# ANT_Miner_CtrlUnit_V1_2.net
KiCad netlist of a schematic drawn in Altium Designer
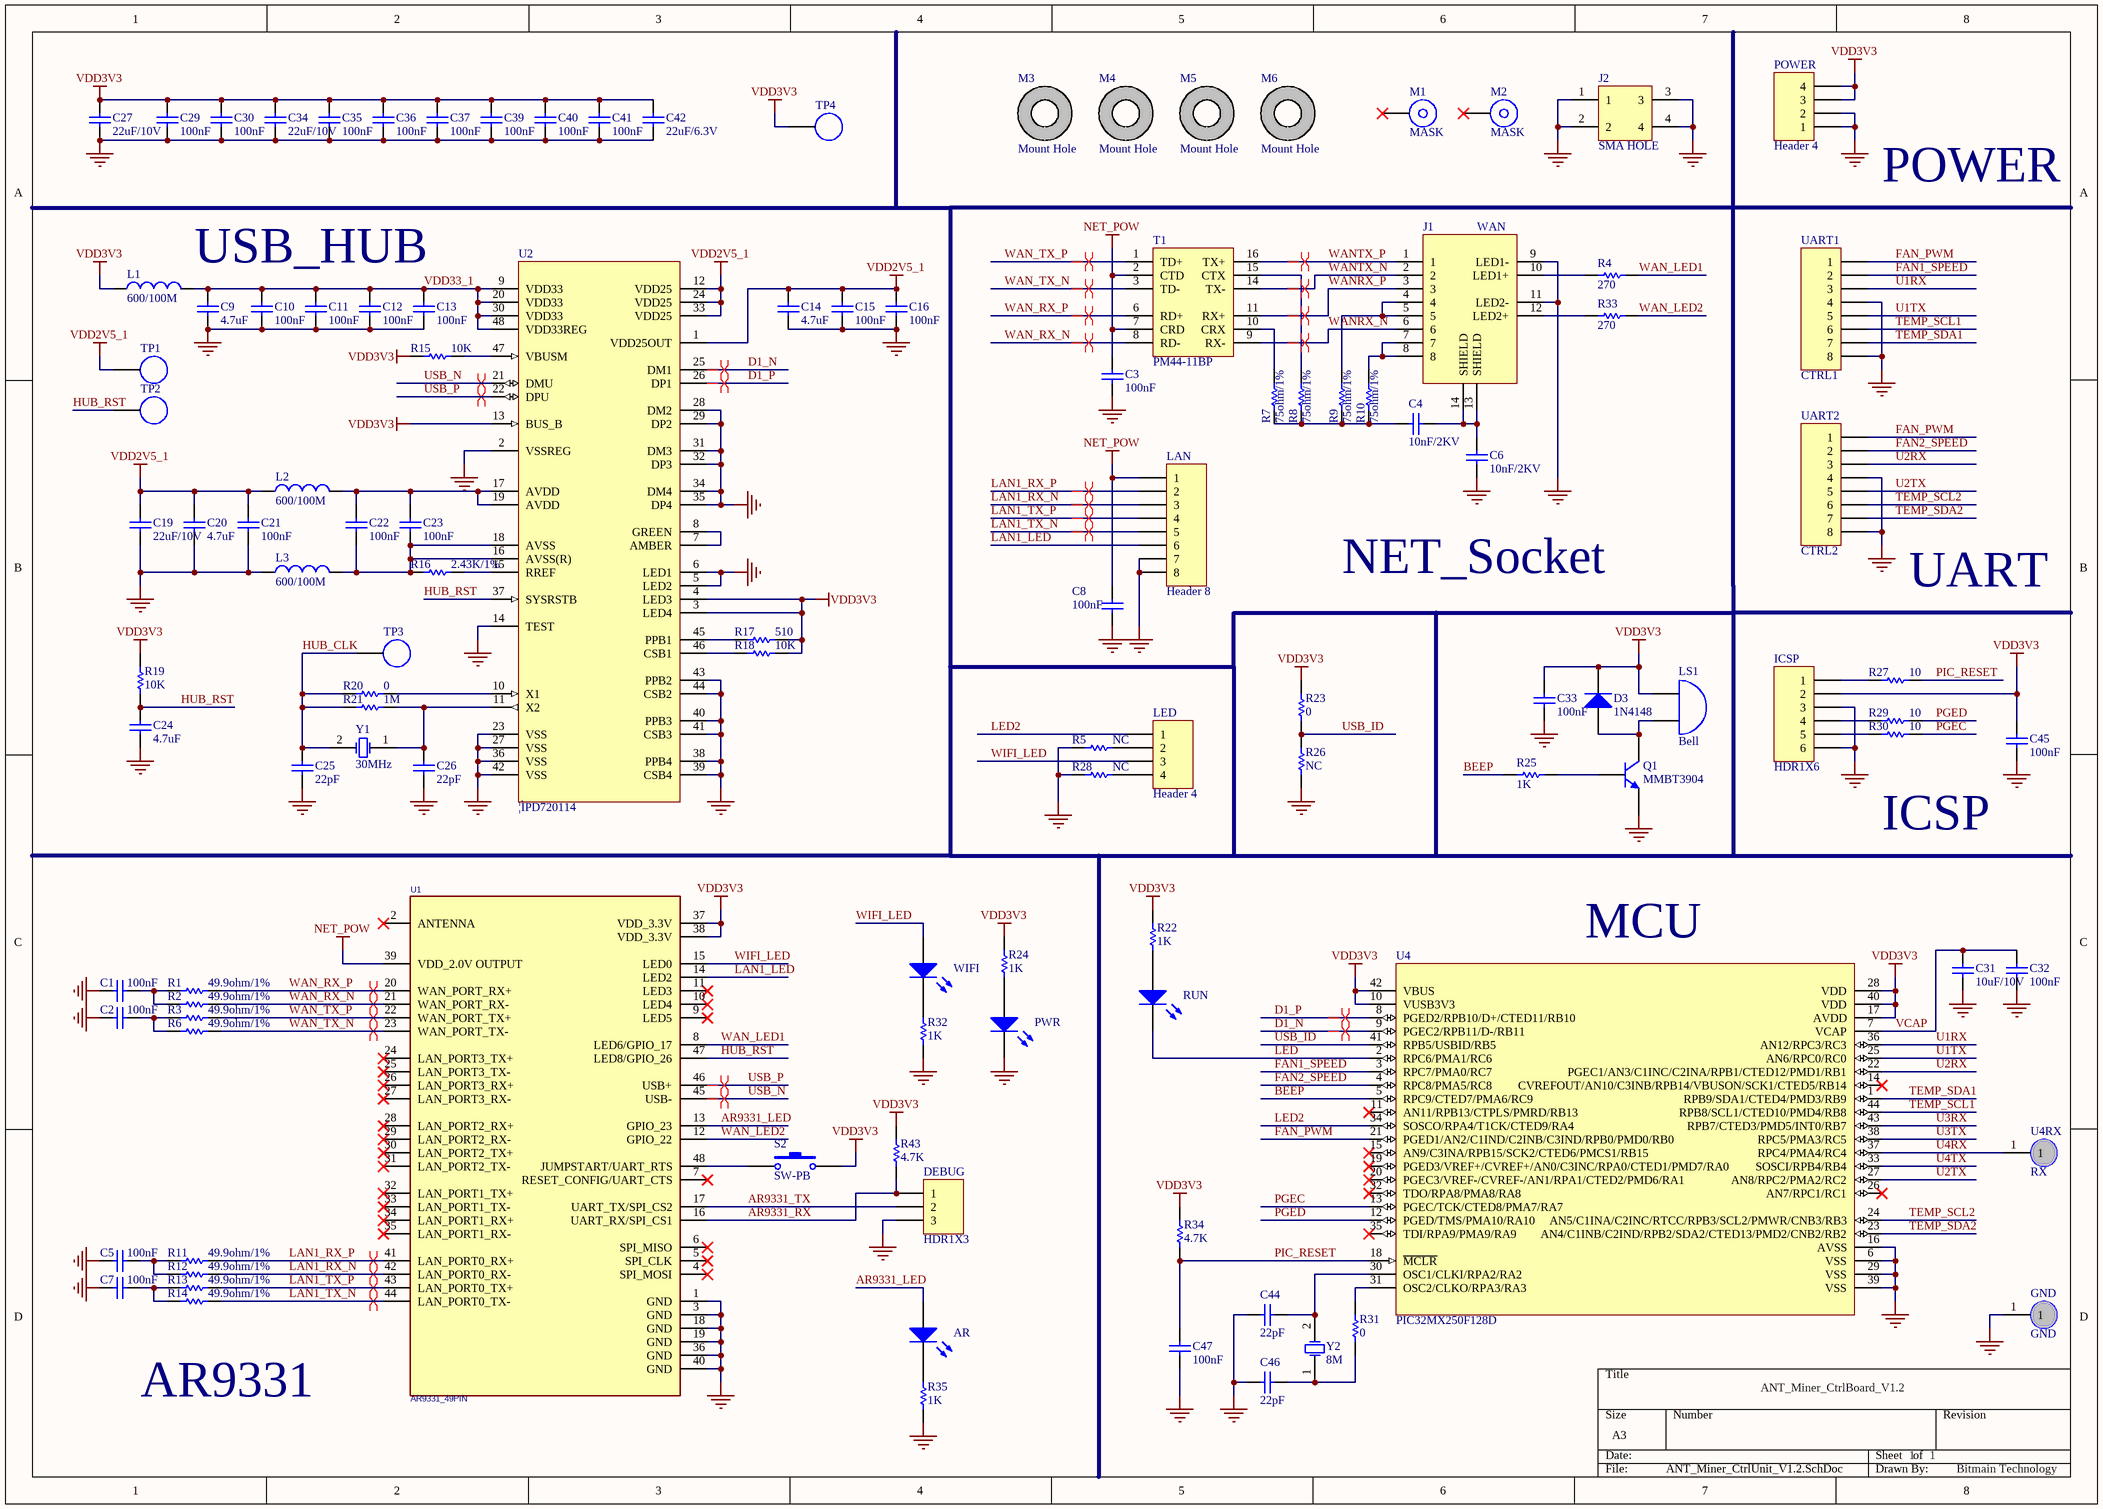
[diagram p0: ANT_Miner_CtrlUnit_V1.2.SchDoc]

(export (version "E")
  (design (tool "Eeschema 10.0.6"))
  (components
    (comp (ref "AR")
      (value "Green")
      (footprint "LED0603(1608)")
      (description "Typical INFRARED GaAs LED")
      (fields (field (name "PUBLISHER") "Altium Limited"))
      (libsource (lib "ANT_Miner_CtrlBoard_V1.1") (part "LED0"))
    )
    (comp (ref "C1")
      (value "100nF")
      (footprint "CC0603(1608)")
      (description "Capacitor (Semiconductor SIM Model)")
      (fields (field (name "PUBLISHER") "Altium Limited"))
      (libsource (lib "ANT_Miner_CtrlBoard_V1.1") (part "Cap Semi"))
    )
    (comp (ref "C2")
      (value "100nF")
      (footprint "CC0603(1608)")
      (description "Capacitor (Semiconductor SIM Model)")
      (fields (field (name "PUBLISHER") "Altium Limited"))
      (libsource (lib "ANT_Miner_CtrlBoard_V1.1") (part "Cap Semi"))
    )
    (comp (ref "C3")
      (value "100nF")
      (footprint "CC0603(1608)")
      (description "Capacitor (Semiconductor SIM Model)")
      (fields (field (name "PUBLISHER") "Altium Limited"))
      (libsource (lib "ANT_Miner_CtrlBoard_V1.1") (part "Cap Semi"))
    )
    (comp (ref "C4")
      (value "10nF/2KV")
      (footprint "1812")
      (description "Capacitor (Semiconductor SIM Model)")
      (fields (field (name "PUBLISHER") "Altium Limited"))
      (libsource (lib "ANT_Miner_CtrlBoard_V1.1") (part "Cap Semi"))
    )
    (comp (ref "C5")
      (value "100nF")
      (footprint "CC0603(1608)")
      (description "Capacitor (Semiconductor SIM Model)")
      (fields (field (name "PUBLISHER") "Altium Limited"))
      (libsource (lib "ANT_Miner_CtrlBoard_V1.1") (part "Cap Semi"))
    )
    (comp (ref "C6")
      (value "10nF/2KV")
      (footprint "1812")
      (description "Capacitor (Semiconductor SIM Model)")
      (fields (field (name "PUBLISHER") "Altium Limited"))
      (libsource (lib "ANT_Miner_CtrlBoard_V1.1") (part "Cap Semi"))
    )
    (comp (ref "C7")
      (value "100nF")
      (footprint "CC0603(1608)")
      (description "Capacitor (Semiconductor SIM Model)")
      (fields (field (name "PUBLISHER") "Altium Limited"))
      (libsource (lib "ANT_Miner_CtrlBoard_V1.1") (part "Cap Semi"))
    )
    (comp (ref "C8")
      (value "100nF")
      (footprint "CC0603(1608)")
      (description "Capacitor (Semiconductor SIM Model)")
      (fields (field (name "PUBLISHER") "Altium Limited"))
      (libsource (lib "ANT_Miner_CtrlBoard_V1.1") (part "Cap Semi"))
    )
    (comp (ref "C9")
      (value "4.7uF")
      (footprint "CC0603(1608)")
      (description "Capacitor (Semiconductor SIM Model)")
      (fields (field (name "PUBLISHER") "Altium Limited"))
      (libsource (lib "ANT_Miner_CtrlBoard_V1.1") (part "Cap Semi"))
    )
    (comp (ref "C10")
      (value "100nF")
      (footprint "CC0603(1608)")
      (description "Capacitor (Semiconductor SIM Model)")
      (fields (field (name "PUBLISHER") "Altium Limited"))
      (libsource (lib "ANT_Miner_CtrlBoard_V1.1") (part "Cap Semi"))
    )
    (comp (ref "C11")
      (value "100nF")
      (footprint "CC0603(1608)")
      (description "Capacitor (Semiconductor SIM Model)")
      (fields (field (name "PUBLISHER") "Altium Limited"))
      (libsource (lib "ANT_Miner_CtrlBoard_V1.1") (part "Cap Semi"))
    )
    (comp (ref "C12")
      (value "100nF")
      (footprint "CC0603(1608)")
      (description "Capacitor (Semiconductor SIM Model)")
      (fields (field (name "PUBLISHER") "Altium Limited"))
      (libsource (lib "ANT_Miner_CtrlBoard_V1.1") (part "Cap Semi"))
    )
    (comp (ref "C13")
      (value "100nF")
      (footprint "CC0603(1608)")
      (description "Capacitor (Semiconductor SIM Model)")
      (fields (field (name "PUBLISHER") "Altium Limited"))
      (libsource (lib "ANT_Miner_CtrlBoard_V1.1") (part "Cap Semi"))
    )
    (comp (ref "C14")
      (value "4.7uF")
      (footprint "CC0603(1608)")
      (description "Capacitor (Semiconductor SIM Model)")
      (fields (field (name "PUBLISHER") "Altium Limited"))
      (libsource (lib "ANT_Miner_CtrlBoard_V1.1") (part "Cap Semi"))
    )
    (comp (ref "C15")
      (value "100nF")
      (footprint "CC0603(1608)")
      (description "Capacitor (Semiconductor SIM Model)")
      (fields (field (name "PUBLISHER") "Altium Limited"))
      (libsource (lib "ANT_Miner_CtrlBoard_V1.1") (part "Cap Semi"))
    )
    (comp (ref "C16")
      (value "100nF")
      (footprint "CC0603(1608)")
      (description "Capacitor (Semiconductor SIM Model)")
      (fields (field (name "PUBLISHER") "Altium Limited"))
      (libsource (lib "ANT_Miner_CtrlBoard_V1.1") (part "Cap Semi"))
    )
    (comp (ref "C19")
      (value "22uF/10V")
      (footprint "CC1210(3225)")
      (description "Capacitor (Semiconductor SIM Model)")
      (fields (field (name "PUBLISHER") "Altium Limited"))
      (libsource (lib "ANT_Miner_CtrlBoard_V1.1") (part "Cap Semi"))
    )
    (comp (ref "C20")
      (value "4.7uF")
      (footprint "CC0603(1608)")
      (description "Capacitor (Semiconductor SIM Model)")
      (fields (field (name "PUBLISHER") "Altium Limited"))
      (libsource (lib "ANT_Miner_CtrlBoard_V1.1") (part "Cap Semi"))
    )
    (comp (ref "C21")
      (value "100nF")
      (footprint "CC0603(1608)")
      (description "Capacitor (Semiconductor SIM Model)")
      (fields (field (name "PUBLISHER") "Altium Limited"))
      (libsource (lib "ANT_Miner_CtrlBoard_V1.1") (part "Cap Semi"))
    )
    (comp (ref "C22")
      (value "100nF")
      (footprint "CC0603(1608)")
      (description "Capacitor (Semiconductor SIM Model)")
      (fields (field (name "PUBLISHER") "Altium Limited"))
      (libsource (lib "ANT_Miner_CtrlBoard_V1.1") (part "Cap Semi"))
    )
    (comp (ref "C23")
      (value "100nF")
      (footprint "CC0603(1608)")
      (description "Capacitor (Semiconductor SIM Model)")
      (fields (field (name "PUBLISHER") "Altium Limited"))
      (libsource (lib "ANT_Miner_CtrlBoard_V1.1") (part "Cap Semi"))
    )
    (comp (ref "C24")
      (value "4.7uF")
      (footprint "CC0603(1608)")
      (description "Capacitor (Semiconductor SIM Model)")
      (fields (field (name "PUBLISHER") "Altium Limited"))
      (libsource (lib "ANT_Miner_CtrlBoard_V1.1") (part "Cap Semi"))
    )
    (comp (ref "C25")
      (value "22pF")
      (footprint "CC0603(1608)")
      (description "Capacitor (Semiconductor SIM Model)")
      (fields (field (name "PUBLISHER") "Altium Limited"))
      (libsource (lib "ANT_Miner_CtrlBoard_V1.1") (part "Cap Semi"))
    )
    (comp (ref "C26")
      (value "22pF")
      (footprint "CC0603(1608)")
      (description "Capacitor (Semiconductor SIM Model)")
      (fields (field (name "PUBLISHER") "Altium Limited"))
      (libsource (lib "ANT_Miner_CtrlBoard_V1.1") (part "Cap Semi"))
    )
    (comp (ref "C27")
      (value "22uF/10V")
      (footprint "CC1210(3225)")
      (description "Capacitor (Semiconductor SIM Model)")
      (fields (field (name "PUBLISHER") "Altium Limited"))
      (libsource (lib "ANT_Miner_CtrlBoard_V1.1") (part "Cap Semi"))
    )
    (comp (ref "C29")
      (value "100nF")
      (footprint "CC0603(1608)")
      (description "Capacitor (Semiconductor SIM Model)")
      (fields (field (name "PUBLISHER") "Altium Limited"))
      (libsource (lib "ANT_Miner_CtrlBoard_V1.1") (part "Cap Semi"))
    )
    (comp (ref "C30")
      (value "100nF")
      (footprint "CC0603(1608)")
      (description "Capacitor (Semiconductor SIM Model)")
      (fields (field (name "PUBLISHER") "Altium Limited"))
      (libsource (lib "ANT_Miner_CtrlBoard_V1.1") (part "Cap Semi"))
    )
    (comp (ref "C31")
      (value "10uF/10V")
      (footprint "CC1210(3225)")
      (description "Capacitor (Semiconductor SIM Model)")
      (fields (field (name "PUBLISHER") "Altium Limited"))
      (libsource (lib "ANT_Miner_CtrlBoard_V1.1") (part "Cap Semi"))
    )
    (comp (ref "C32")
      (value "100nF")
      (footprint "CC0603(1608)")
      (description "Capacitor (Semiconductor SIM Model)")
      (fields (field (name "PUBLISHER") "Altium Limited"))
      (libsource (lib "ANT_Miner_CtrlBoard_V1.1") (part "Cap Semi"))
    )
    (comp (ref "C33")
      (value "100nF")
      (footprint "CC0603(1608)")
      (description "Capacitor (Semiconductor SIM Model)")
      (fields (field (name "PUBLISHER") "Altium Limited"))
      (libsource (lib "ANT_Miner_CtrlBoard_V1.1") (part "Cap Semi"))
    )
    (comp (ref "C34")
      (value "22uF/10V")
      (footprint "CC1210(3225)")
      (description "Capacitor (Semiconductor SIM Model)")
      (fields (field (name "PUBLISHER") "Altium Limited"))
      (libsource (lib "ANT_Miner_CtrlBoard_V1.1") (part "Cap Semi"))
    )
    (comp (ref "C35")
      (value "100nF")
      (footprint "CC0603(1608)")
      (description "Capacitor (Semiconductor SIM Model)")
      (fields (field (name "PUBLISHER") "Altium Limited"))
      (libsource (lib "ANT_Miner_CtrlBoard_V1.1") (part "Cap Semi"))
    )
    (comp (ref "C36")
      (value "100nF")
      (footprint "CC0603(1608)")
      (description "Capacitor (Semiconductor SIM Model)")
      (fields (field (name "PUBLISHER") "Altium Limited"))
      (libsource (lib "ANT_Miner_CtrlBoard_V1.1") (part "Cap Semi"))
    )
    (comp (ref "C37")
      (value "100nF")
      (footprint "CC0603(1608)")
      (description "Capacitor (Semiconductor SIM Model)")
      (fields (field (name "PUBLISHER") "Altium Limited"))
      (libsource (lib "ANT_Miner_CtrlBoard_V1.1") (part "Cap Semi"))
    )
    (comp (ref "C39")
      (value "100nF")
      (footprint "CC0603(1608)")
      (description "Capacitor (Semiconductor SIM Model)")
      (fields (field (name "PUBLISHER") "Altium Limited"))
      (libsource (lib "ANT_Miner_CtrlBoard_V1.1") (part "Cap Semi"))
    )
    (comp (ref "C40")
      (value "100nF")
      (footprint "CC0603(1608)")
      (description "Capacitor (Semiconductor SIM Model)")
      (fields (field (name "PUBLISHER") "Altium Limited"))
      (libsource (lib "ANT_Miner_CtrlBoard_V1.1") (part "Cap Semi"))
    )
    (comp (ref "C41")
      (value "100nF")
      (footprint "CC0603(1608)")
      (description "Capacitor (Semiconductor SIM Model)")
      (fields (field (name "PUBLISHER") "Altium Limited"))
      (libsource (lib "ANT_Miner_CtrlBoard_V1.1") (part "Cap Semi"))
    )
    (comp (ref "C42")
      (value "22uF/6.3V")
      (footprint "CC1210(3225)")
      (description "Capacitor (Semiconductor SIM Model)")
      (fields (field (name "PUBLISHER") "Altium Limited"))
      (libsource (lib "ANT_Miner_CtrlBoard_V1.1") (part "Cap Semi"))
    )
    (comp (ref "C44")
      (value "22pF")
      (footprint "CC0603(1608)")
      (description "Capacitor (Semiconductor SIM Model)")
      (fields (field (name "PUBLISHER") "Altium Limited"))
      (libsource (lib "ANT_Miner_CtrlBoard_V1.1") (part "Cap Semi"))
    )
    (comp (ref "C45")
      (value "100nF")
      (footprint "CC0603(1608)")
      (description "Capacitor (Semiconductor SIM Model)")
      (fields (field (name "PUBLISHER") "Altium Limited"))
      (libsource (lib "ANT_Miner_CtrlBoard_V1.1") (part "Cap Semi"))
    )
    (comp (ref "C46")
      (value "22pF")
      (footprint "CC0603(1608)")
      (description "Capacitor (Semiconductor SIM Model)")
      (fields (field (name "PUBLISHER") "Altium Limited"))
      (libsource (lib "ANT_Miner_CtrlBoard_V1.1") (part "Cap Semi"))
    )
    (comp (ref "C47")
      (value "100nF")
      (footprint "CC0603(1608)")
      (description "Capacitor (Semiconductor SIM Model)")
      (fields (field (name "PUBLISHER") "Altium Limited"))
      (libsource (lib "ANT_Miner_CtrlBoard_V1.1") (part "Cap Semi"))
    )
    (comp (ref "D3")
      (value "1N4148")
      (footprint "DIODE0805")
      (description "High Conductance Fast Diode")
      (fields (field (name "PUBLISHER") "Altium Limited"))
      (libsource (lib "ANT_Miner_CtrlBoard_V1.1") (part "Diode 1N4148"))
    )
    (comp (ref "DEBUG")
      (value "HDR1X3")
      (footprint "HDR1X3")
      (description "Header, 3-Pin")
      (fields (field (name "PUBLISHER") "Altium Limited"))
      (libsource (lib "ANT_Miner_CtrlBoard_V1.1") (part "Header 3"))
    )
    (comp (ref "GND") (value "GND") (footprint "TP_DIP_1.5mm") (libsource (lib "ANT_Miner_V1.3") (part "TP")))
    (comp (ref "ICSP")
      (value "HDR1X6")
      (footprint "HDR1X6")
      (description "Header, 6-Pin")
      (fields (field (name "PUBLISHER") "Altium Limited"))
      (libsource (lib "ANT_Miner_CtrlBoard_V1.1") (part "Header 6"))
    )
    (comp (ref "J1")
      (value "WAN")
      (footprint "RJ45_2LED_DIP")
      (description "RJ45,DUAL LED,DIP")
      (libsource (lib "ANT_Miner_CtrlBoard_V1.1") (part "RJ45-DIP"))
    )
    (comp (ref "J2")
      (value "SMA HOLE")
      (footprint "SMA_HOLE")
      (description "SMA Socket Assembly Hole.")
      (libsource (lib "ANT_Miner_CtrlBoard_V1.1") (part "SMA_HOLE"))
    )
    (comp (ref "L1")
      (value "600/100M")
      (footprint "INDC1608L")
      (description "Inductor")
      (fields (field (name "PUBLISHER") "Altium Limited"))
      (libsource (lib "ANT_Miner_CtrlBoard_V1.1") (part "Inductor"))
    )
    (comp (ref "L2")
      (value "600/100M")
      (footprint "INDC1608L")
      (description "Inductor")
      (fields (field (name "PUBLISHER") "Altium Limited"))
      (libsource (lib "ANT_Miner_CtrlBoard_V1.1") (part "Inductor"))
    )
    (comp (ref "L3")
      (value "600/100M")
      (footprint "INDC1608L")
      (description "Inductor")
      (fields (field (name "PUBLISHER") "Altium Limited"))
      (libsource (lib "ANT_Miner_CtrlBoard_V1.1") (part "Inductor"))
    )
    (comp (ref "LAN")
      (value "Header 8")
      (footprint "8Pin_180")
      (description "Header, 8-Pin")
      (fields (field (name "PUBLISHER") "Altium Limited"))
      (libsource (lib "ANT_Miner_CtrlBoard_V1.1") (part "Header 8"))
    )
    (comp (ref "LED")
      (value "Header 4")
      (footprint "4Pin_180")
      (description "Header, 4-Pin")
      (fields (field (name "PUBLISHER") "Altium Limited"))
      (libsource (lib "ANT_Miner_CtrlBoard_V1.1") (part "Header 4"))
    )
    (comp (ref "LS1")
      (value "Bell")
      (footprint "YR5025A")
      (description "Electrical Bell")
      (fields (field (name "PUBLISHER") "Altium Limited"))
      (libsource (lib "ANT_Miner_CtrlBoard_V1.1") (part "Bell"))
    )
    (comp (ref "M1")
      (value "MASK")
      (footprint "MASK")
      (libsource (lib "ANT_Miner_CtrlBoard_V1.1") (part "MASK"))
    )
    (comp (ref "M2")
      (value "MASK")
      (footprint "MASK")
      (libsource (lib "ANT_Miner_CtrlBoard_V1.1") (part "MASK"))
    )
    (comp (ref "M3")
      (value "Mount Hole")
      (footprint "HOLE_3.2")
      (libsource (lib "ANT_Miner_CtrlBoard_V1.1") (part "M_Hole"))
    )
    (comp (ref "M4")
      (value "Mount Hole")
      (footprint "HOLE_3.2")
      (libsource (lib "ANT_Miner_CtrlBoard_V1.1") (part "M_Hole"))
    )
    (comp (ref "M5")
      (value "Mount Hole")
      (footprint "HOLE_3.2")
      (libsource (lib "ANT_Miner_CtrlBoard_V1.1") (part "M_Hole"))
    )
    (comp (ref "M6")
      (value "Mount Hole")
      (footprint "HOLE_3.2")
      (libsource (lib "ANT_Miner_CtrlBoard_V1.1") (part "M_Hole"))
    )
    (comp (ref "POWER")
      (value "Header 4")
      (footprint "4Pin_180")
      (description "Header, 4-Pin")
      (fields (field (name "PUBLISHER") "Altium Limited"))
      (libsource (lib "") (part "Header 4_1"))
    )
    (comp (ref "PWR")
      (value "Red")
      (footprint "LED0603(1608)")
      (description "Typical INFRARED GaAs LED")
      (fields (field (name "PUBLISHER") "Altium Limited"))
      (libsource (lib "ANT_Miner_CtrlBoard_V1.1") (part "LED0"))
    )
    (comp (ref "Q1")
      (value "MMBT3904")
      (footprint "SOT23_L")
      (description "NPN Switching Transistor")
      (fields (field (name "PUBLISHER") "Altium Limited"))
      (libsource (lib "ANT_Miner_CtrlBoard_V1.1") (part "MMBT3904"))
    )
    (comp (ref "R1")
      (value "49.9ohm/1%")
      (footprint "RR0603(1608)")
      (description "Resistor")
      (libsource (lib "") (part "Res1_1"))
    )
    (comp (ref "R2")
      (value "49.9ohm/1%")
      (footprint "RR0603(1608)")
      (description "Resistor")
      (libsource (lib "") (part "Res1_1"))
    )
    (comp (ref "R3")
      (value "49.9ohm/1%")
      (footprint "RR0603(1608)")
      (description "Resistor")
      (libsource (lib "") (part "Res1_1"))
    )
    (comp (ref "R4")
      (value "270")
      (footprint "RR0603(1608)")
      (description "Resistor")
      (libsource (lib "") (part "Res1_1"))
    )
    (comp (ref "R5")
      (value "NC")
      (footprint "RR0603(1608)")
      (description "Resistor")
      (libsource (lib "") (part "Res1_1"))
    )
    (comp (ref "R6")
      (value "49.9ohm/1%")
      (footprint "RR0603(1608)")
      (description "Resistor")
      (libsource (lib "") (part "Res1_1"))
    )
    (comp (ref "R7")
      (value "75ohm/1%")
      (footprint "RR0603(1608)")
      (description "Resistor")
      (fields (field (name "PUBLISHER") "Altium Limited"))
      (libsource (lib "ANT_Miner_CtrlBoard_V1.1") (part "Res1"))
    )
    (comp (ref "R8")
      (value "75ohm/1%")
      (footprint "RR0603(1608)")
      (description "Resistor")
      (fields (field (name "PUBLISHER") "Altium Limited"))
      (libsource (lib "ANT_Miner_CtrlBoard_V1.1") (part "Res1"))
    )
    (comp (ref "R9")
      (value "75ohm/1%")
      (footprint "RR0603(1608)")
      (description "Resistor")
      (fields (field (name "PUBLISHER") "Altium Limited"))
      (libsource (lib "ANT_Miner_CtrlBoard_V1.1") (part "Res1"))
    )
    (comp (ref "R10")
      (value "75ohm/1%")
      (footprint "RR0603(1608)")
      (description "Resistor")
      (fields (field (name "PUBLISHER") "Altium Limited"))
      (libsource (lib "ANT_Miner_CtrlBoard_V1.1") (part "Res1"))
    )
    (comp (ref "R11")
      (value "49.9ohm/1%")
      (footprint "RR0603(1608)")
      (description "Resistor")
      (libsource (lib "") (part "Res1_1"))
    )
    (comp (ref "R12")
      (value "49.9ohm/1%")
      (footprint "RR0603(1608)")
      (description "Resistor")
      (libsource (lib "") (part "Res1_1"))
    )
    (comp (ref "R13")
      (value "49.9ohm/1%")
      (footprint "RR0603(1608)")
      (description "Resistor")
      (libsource (lib "") (part "Res1_1"))
    )
    (comp (ref "R14")
      (value "49.9ohm/1%")
      (footprint "RR0603(1608)")
      (description "Resistor")
      (libsource (lib "") (part "Res1_1"))
    )
    (comp (ref "R15")
      (value "10K")
      (footprint "RR0603(1608)")
      (description "Resistor")
      (libsource (lib "") (part "Res1_1"))
    )
    (comp (ref "R16")
      (value "2.43K/1%")
      (footprint "RR0603(1608)")
      (description "Resistor")
      (libsource (lib "") (part "Res1_1"))
    )
    (comp (ref "R17")
      (value "510")
      (footprint "RR0603(1608)")
      (description "Resistor")
      (libsource (lib "") (part "Res1_1"))
    )
    (comp (ref "R18")
      (value "10K")
      (footprint "RR0603(1608)")
      (description "Resistor")
      (libsource (lib "") (part "Res1_1"))
    )
    (comp (ref "R19")
      (value "10K")
      (footprint "RR0603(1608)")
      (description "Resistor")
      (libsource (lib "") (part "Res1_1"))
    )
    (comp (ref "R20")
      (value "0")
      (footprint "RR0603(1608)")
      (description "Resistor")
      (libsource (lib "") (part "Res1_1"))
    )
    (comp (ref "R21")
      (value "1M")
      (footprint "RR0603(1608)")
      (description "Resistor")
      (libsource (lib "") (part "Res1_1"))
    )
    (comp (ref "R22")
      (value "1K")
      (footprint "RR0603(1608)")
      (description "Resistor")
      (fields (field (name "PUBLISHER") "Altium Limited"))
      (libsource (lib "ANT_Miner_CtrlBoard_V1.1") (part "Res1"))
    )
    (comp (ref "R23")
      (value "0")
      (footprint "RR0603(1608)")
      (description "Resistor")
      (fields (field (name "PUBLISHER") "Altium Limited"))
      (libsource (lib "ANT_Miner_CtrlBoard_V1.1") (part "Res1"))
    )
    (comp (ref "R24")
      (value "1K")
      (footprint "RR0603(1608)")
      (description "Resistor")
      (libsource (lib "") (part "Res1_1"))
    )
    (comp (ref "R25")
      (value "1K")
      (footprint "RR0603(1608)")
      (description "Resistor")
      (fields (field (name "PUBLISHER") "Altium Limited"))
      (libsource (lib "ANT_Miner_CtrlBoard_V1.1") (part "Res1"))
    )
    (comp (ref "R26")
      (value "NC")
      (footprint "RR0603(1608)")
      (description "Resistor")
      (fields (field (name "PUBLISHER") "Altium Limited"))
      (libsource (lib "ANT_Miner_CtrlBoard_V1.1") (part "Res1"))
    )
    (comp (ref "R27")
      (value "10")
      (footprint "RR0603(1608)")
      (description "Resistor")
      (fields (field (name "PUBLISHER") "Altium Limited"))
      (libsource (lib "ANT_Miner_CtrlBoard_V1.1") (part "Res1"))
    )
    (comp (ref "R28")
      (value "NC")
      (footprint "RR0603(1608)")
      (description "Resistor")
      (libsource (lib "") (part "Res1_1"))
    )
    (comp (ref "R29")
      (value "10")
      (footprint "RR0603(1608)")
      (description "Resistor")
      (fields (field (name "PUBLISHER") "Altium Limited"))
      (libsource (lib "ANT_Miner_CtrlBoard_V1.1") (part "Res1"))
    )
    (comp (ref "R30")
      (value "10")
      (footprint "RR0603(1608)")
      (description "Resistor")
      (fields (field (name "PUBLISHER") "Altium Limited"))
      (libsource (lib "ANT_Miner_CtrlBoard_V1.1") (part "Res1"))
    )
    (comp (ref "R31")
      (value "0")
      (footprint "RR0603(1608)")
      (description "Resistor")
      (fields (field (name "PUBLISHER") "Altium Limited"))
      (libsource (lib "ANT_Miner_CtrlBoard_V1.1") (part "Res1"))
    )
    (comp (ref "R32")
      (value "1K")
      (footprint "RR0603(1608)")
      (description "Resistor")
      (libsource (lib "") (part "Res1_1"))
    )
    (comp (ref "R33")
      (value "270")
      (footprint "RR0603(1608)")
      (description "Resistor")
      (libsource (lib "") (part "Res1_1"))
    )
    (comp (ref "R34")
      (value "4.7K")
      (footprint "RR0603(1608)")
      (description "Resistor")
      (fields (field (name "PUBLISHER") "Altium Limited"))
      (libsource (lib "ANT_Miner_CtrlBoard_V1.1") (part "Res1"))
    )
    (comp (ref "R35")
      (value "1K")
      (footprint "RR0603(1608)")
      (description "Resistor")
      (libsource (lib "") (part "Res1_1"))
    )
    (comp (ref "R43")
      (value "4.7K")
      (footprint "RR0603(1608)")
      (description "Resistor")
      (fields (field (name "PUBLISHER") "Altium Limited"))
      (libsource (lib "ANT_Miner_CtrlBoard_V1.1") (part "Res1"))
    )
    (comp (ref "RUN")
      (value "Green")
      (footprint "LED0603(1608)")
      (description "Typical INFRARED GaAs LED")
      (fields (field (name "PUBLISHER") "Altium Limited"))
      (libsource (lib "ANT_Miner_CtrlBoard_V1.1") (part "LED0"))
    )
    (comp (ref "S2")
      (value "SW-PB")
      (footprint "SWITCH_3x4")
      (description "Switch")
      (fields (field (name "PUBLISHER") "Altium Limited"))
      (libsource (lib "ANT_Miner_CtrlBoard_V1.1") (part "SW-PB"))
    )
    (comp (ref "T1")
      (value "PM44-11BP")
      (footprint "PM44-11BP")
      (libsource (lib "ANT_Miner_CtrlBoard_V1.1") (part "PM44-11BP"))
    )
    (comp (ref "TP1")
      (value "TP")
      (footprint "TP2")
      (libsource (lib "ANT_Miner_CtrlBoard_V1.1") (part "TP2"))
    )
    (comp (ref "TP2")
      (value "TP")
      (footprint "TP2")
      (libsource (lib "ANT_Miner_CtrlBoard_V1.1") (part "TP2"))
    )
    (comp (ref "TP3")
      (value "TP")
      (footprint "TP2")
      (libsource (lib "ANT_Miner_CtrlBoard_V1.1") (part "TP2"))
    )
    (comp (ref "TP4")
      (value "TP")
      (footprint "TP2")
      (libsource (lib "ANT_Miner_CtrlBoard_V1.1") (part "TP2"))
    )
    (comp (ref "U1")
      (value "AR9331_49PIN")
      (footprint "AR9331_49PIN")
      (libsource (lib "ANT_Miner_CtrlBoard_V1.1") (part "AR9331_49PIN"))
    )
    (comp (ref "U2")
      (value "μPD720114")
      (footprint "TQFP48_L")
      (libsource (lib "ANT_Miner_CtrlBoard_V1.1") (part "uPD720114"))
    )
    (comp (ref "U4")
      (value "PIC32MX250F128D")
      (footprint "TQFP44_L")
      (libsource (lib "ANT_Miner_CtrlBoard_V1.1") (part "PIC32MX250F128D"))
    )
    (comp (ref "U4RX") (value "RX") (footprint "TP_DIP_1.5mm") (libsource (lib "ANT_Miner_V1.3") (part "TP")))
    (comp (ref "UART1")
      (value "CTRL1")
      (footprint "8Pin_180")
      (description "Header, 8-Pin")
      (fields (field (name "PUBLISHER") "Altium Limited"))
      (libsource (lib "") (part "Header 8_1"))
    )
    (comp (ref "UART2")
      (value "CTRL2")
      (footprint "8Pin_180")
      (description "Header, 8-Pin")
      (fields (field (name "PUBLISHER") "Altium Limited"))
      (libsource (lib "") (part "Header 8_1"))
    )
    (comp (ref "WIFI")
      (value "Green")
      (footprint "LED0603(1608)")
      (description "Typical INFRARED GaAs LED")
      (fields (field (name "PUBLISHER") "Altium Limited"))
      (libsource (lib "ANT_Miner_CtrlBoard_V1.1") (part "LED0"))
    )
    (comp (ref "Y1")
      (value "30MHz")
      (footprint "4SMX")
      (description "Crystal Oscillator")
      (fields (field (name "PUBLISHER") "Altium Limited"))
      (libsource (lib "ANT_Miner_CtrlBoard_V1.1") (part "XTAL"))
    )
    (comp (ref "Y2")
      (value "8M")
      (footprint "4SMX")
      (description "Crystal Oscillator")
      (fields (field (name "PUBLISHER") "Altium Limited"))
      (libsource (lib "ANT_Miner_CtrlBoard_V1.1") (part "XTAL"))
    )
  )
  (nets
    (net (code "1") (name "/AR9331_LED") (class "Default")
      (node (ref "AR") (pin "1") (pinfunction "A_1") (pintype "passive"))
      (node (ref "U1") (pin "13") (pinfunction "GPIO_23_13") (pintype "passive"))
    )
    (net (code "2") (name "/AR9331_RX") (class "Default")
      (node (ref "DEBUG") (pin "1") (pinfunction "1_1") (pintype "passive"))
      (node (ref "R43") (pin "1") (pinfunction "1_1") (pintype "passive"))
      (node (ref "U1") (pin "16") (pinfunction "UART_RX/SPI_CS1_16") (pintype "passive"))
    )
    (net (code "3") (name "/AR9331_TX") (class "Default")
      (node (ref "DEBUG") (pin "2") (pinfunction "2_2") (pintype "passive"))
      (node (ref "U1") (pin "17") (pinfunction "UART_TX/SPI_CS2_17") (pintype "passive"))
    )
    (net (code "4") (name "/BEEP") (class "Default")
      (node (ref "R25") (pin "2") (pinfunction "2_2") (pintype "passive"))
      (node (ref "U4") (pin "5") (pinfunction "RPC9/CTED7/PMA6/RC9_5") (pintype "bidirectional"))
    )
    (net (code "5") (name "/D1_N") (class "Default")
      (node (ref "U2") (pin "25") (pinfunction "DM1_25") (pintype "passive"))
      (node (ref "U4") (pin "9") (pinfunction "PGEC2/RPB11/D-/RB11_9") (pintype "bidirectional"))
    )
    (net (code "6") (name "/D1_P") (class "Default")
      (node (ref "U2") (pin "26") (pinfunction "DP1_26") (pintype "passive"))
      (node (ref "U4") (pin "8") (pinfunction "PGED2/RPB10/D+/CTED11/RB10_8") (pintype "bidirectional"))
    )
    (net (code "7") (name "/FAN1_SPEED") (class "Default")
      (node (ref "U4") (pin "3") (pinfunction "RPC7/PMA0/RC7_3") (pintype "bidirectional"))
      (node (ref "UART1") (pin "2") (pinfunction "2_2") (pintype "passive"))
    )
    (net (code "8") (name "/FAN2_SPEED") (class "Default")
      (node (ref "U4") (pin "4") (pinfunction "RPC8/PMA5/RC8_4") (pintype "bidirectional"))
      (node (ref "UART2") (pin "2") (pinfunction "2_2") (pintype "passive"))
    )
    (net (code "9") (name "/FAN_PWM") (class "Default")
      (node (ref "U4") (pin "21") (pinfunction "PGED1/AN2/C1IND/C2INB/C3IND/RPB0/PMD0/RB0_21") (pintype "bidirectional"))
      (node (ref "UART1") (pin "1") (pinfunction "1_1") (pintype "passive"))
      (node (ref "UART2") (pin "1") (pinfunction "1_1") (pintype "passive"))
    )
    (net (code "10") (name "/HUB_CLK") (class "Default")
      (node (ref "C25") (pin "2") (pinfunction "2_2") (pintype "passive"))
      (node (ref "R20") (pin "2") (pinfunction "2_2") (pintype "passive"))
      (node (ref "R21") (pin "2") (pinfunction "2_2") (pintype "passive"))
      (node (ref "TP3") (pin "1") (pinfunction "1_1") (pintype "passive"))
      (node (ref "Y1") (pin "2") (pinfunction "OSC2_2") (pintype "passive"))
    )
    (net (code "11") (name "/HUB_RST") (class "Default")
      (node (ref "C24") (pin "2") (pinfunction "2_2") (pintype "passive"))
      (node (ref "R19") (pin "1") (pinfunction "1_1") (pintype "passive"))
      (node (ref "TP2") (pin "1") (pinfunction "1_1") (pintype "passive"))
      (node (ref "U1") (pin "47") (pinfunction "LED8/GPIO_26_47") (pintype "passive"))
      (node (ref "U2") (pin "37") (pinfunction "SYSRSTB_37") (pintype "input"))
    )
    (net (code "12") (name "/LAN1_LED") (class "Default")
      (node (ref "LAN") (pin "6") (pinfunction "6_6") (pintype "passive"))
      (node (ref "U1") (pin "14") (pinfunction "LED2_14") (pintype "passive"))
    )
    (net (code "13") (name "/LAN1_RX_N") (class "Default")
      (node (ref "LAN") (pin "3") (pinfunction "3_3") (pintype "passive"))
      (node (ref "R12") (pin "2") (pinfunction "2_2") (pintype "passive"))
      (node (ref "U1") (pin "42") (pinfunction "LAN_PORT0_RX-_42") (pintype "passive"))
    )
    (net (code "14") (name "/LAN1_RX_P") (class "Default")
      (node (ref "LAN") (pin "2") (pinfunction "2_2") (pintype "passive"))
      (node (ref "R11") (pin "2") (pinfunction "2_2") (pintype "passive"))
      (node (ref "U1") (pin "41") (pinfunction "LAN_PORT0_RX+_41") (pintype "passive"))
    )
    (net (code "15") (name "/LAN1_TX_N") (class "Default")
      (node (ref "LAN") (pin "5") (pinfunction "5_5") (pintype "passive"))
      (node (ref "R14") (pin "2") (pinfunction "2_2") (pintype "passive"))
      (node (ref "U1") (pin "44") (pinfunction "LAN_PORT0_TX-_44") (pintype "passive"))
    )
    (net (code "16") (name "/LAN1_TX_P") (class "Default")
      (node (ref "LAN") (pin "4") (pinfunction "4_4") (pintype "passive"))
      (node (ref "R13") (pin "2") (pinfunction "2_2") (pintype "passive"))
      (node (ref "U1") (pin "43") (pinfunction "LAN_PORT0_TX+_43") (pintype "passive"))
    )
    (net (code "17") (name "/LED") (class "Default")
      (node (ref "RUN") (pin "2") (pinfunction "K_2") (pintype "passive"))
      (node (ref "U4") (pin "2") (pinfunction "RPC6/PMA1/RC6_2") (pintype "bidirectional"))
    )
    (net (code "18") (name "/LED2") (class "Default")
      (node (ref "LED") (pin "1") (pinfunction "1_1") (pintype "passive"))
      (node (ref "U4") (pin "34") (pinfunction "SOSCO/RPA4/T1CK/CTED9/RA4_34") (pintype "bidirectional"))
    )
    (net (code "19") (name "/PGEC") (class "Default")
      (node (ref "R30") (pin "1") (pinfunction "1_1") (pintype "passive"))
      (node (ref "U4") (pin "13") (pinfunction "PGEC/TCK/CTED8/PMA7/RA7_13") (pintype "bidirectional"))
    )
    (net (code "20") (name "/PGED") (class "Default")
      (node (ref "R29") (pin "1") (pinfunction "1_1") (pintype "passive"))
      (node (ref "U4") (pin "12") (pinfunction "PGED/TMS/PMA10/RA10_12") (pintype "bidirectional"))
    )
    (net (code "21") (name "/PIC_RESET") (class "Default")
      (node (ref "C47") (pin "2") (pinfunction "2_2") (pintype "passive"))
      (node (ref "R27") (pin "1") (pinfunction "1_1") (pintype "passive"))
      (node (ref "R34") (pin "1") (pinfunction "1_1") (pintype "passive"))
      (node (ref "U4") (pin "18") (pinfunction "~{MCLR}_18") (pintype "input"))
    )
    (net (code "22") (name "/TEMP_SCL1") (class "Default")
      (node (ref "U4") (pin "44") (pinfunction "RPB8/SCL1/CTED10/PMD4/RB8_44") (pintype "bidirectional"))
      (node (ref "UART1") (pin "6") (pinfunction "6_6") (pintype "passive"))
    )
    (net (code "23") (name "/TEMP_SCL2") (class "Default")
      (node (ref "U4") (pin "24") (pinfunction "AN5/C1INA/C2INC/RTCC/RPB3/SCL2/PMWR/CNB3/RB3_24") (pintype "bidirectional"))
      (node (ref "UART2") (pin "6") (pinfunction "6_6") (pintype "passive"))
    )
    (net (code "24") (name "/TEMP_SDA1") (class "Default")
      (node (ref "U4") (pin "1") (pinfunction "RPB9/SDA1/CTED4/PMD3/RB9_1") (pintype "bidirectional"))
      (node (ref "UART1") (pin "7") (pinfunction "7_7") (pintype "passive"))
    )
    (net (code "25") (name "/TEMP_SDA2") (class "Default")
      (node (ref "U4") (pin "23") (pinfunction "AN4/C1INB/C2IND/RPB2/SDA2/CTED13/PMD2/CNB2/RB2_23") (pintype "bidirectional"))
      (node (ref "UART2") (pin "7") (pinfunction "7_7") (pintype "passive"))
    )
    (net (code "26") (name "/U1RX") (class "Default")
      (node (ref "U4") (pin "36") (pinfunction "AN12/RPC3/RC3_36") (pintype "bidirectional"))
      (node (ref "UART1") (pin "3") (pinfunction "3_3") (pintype "passive"))
    )
    (net (code "27") (name "/U1TX") (class "Default")
      (node (ref "U4") (pin "25") (pinfunction "AN6/RPC0/RC0_25") (pintype "bidirectional"))
      (node (ref "UART1") (pin "5") (pinfunction "5_5") (pintype "passive"))
    )
    (net (code "28") (name "/U2RX") (class "Default")
      (node (ref "U4") (pin "22") (pinfunction "PGEC1/AN3/C1INC/C2INA/RPB1/CTED12/PMD1/RB1_22") (pintype "bidirectional"))
      (node (ref "UART2") (pin "3") (pinfunction "3_3") (pintype "passive"))
    )
    (net (code "29") (name "/U2TX") (class "Default")
      (node (ref "U4") (pin "27") (pinfunction "AN8/RPC2/PMA2/RC2_27") (pintype "bidirectional"))
      (node (ref "UART2") (pin "5") (pinfunction "5_5") (pintype "passive"))
    )
    (net (code "30") (name "/U3RX") (class "Default")
      (node (ref "U4") (pin "43") (pinfunction "RPB7/CTED3/PMD5/INT0/RB7_43") (pintype "bidirectional"))
    )
    (net (code "31") (name "/U3TX") (class "Default")
      (node (ref "U4") (pin "38") (pinfunction "RPC5/PMA3/RC5_38") (pintype "bidirectional"))
    )
    (net (code "32") (name "/U4RX") (class "Default")
      (node (ref "U4") (pin "37") (pinfunction "RPC4/PMA4/RC4_37") (pintype "bidirectional"))
      (node (ref "U4RX") (pin "1") (pinfunction "1_1") (pintype "passive"))
    )
    (net (code "33") (name "/U4TX") (class "Default")
      (node (ref "U4") (pin "33") (pinfunction "SOSCI/RPB4/RB4_33") (pintype "bidirectional"))
    )
    (net (code "34") (name "/USB_ID") (class "Default")
      (node (ref "R23") (pin "1") (pinfunction "1_1") (pintype "passive"))
      (node (ref "R26") (pin "2") (pinfunction "2_2") (pintype "passive"))
      (node (ref "U4") (pin "41") (pinfunction "RPB5/USBID/RB5_41") (pintype "bidirectional"))
    )
    (net (code "35") (name "/USB_N") (class "Default")
      (node (ref "U1") (pin "45") (pinfunction "USB-_45") (pintype "passive"))
      (node (ref "U2") (pin "21") (pinfunction "DMU_21") (pintype "bidirectional"))
    )
    (net (code "36") (name "/USB_P") (class "Default")
      (node (ref "U1") (pin "46") (pinfunction "USB+_46") (pintype "passive"))
      (node (ref "U2") (pin "22") (pinfunction "DPU_22") (pintype "bidirectional"))
    )
    (net (code "37") (name "/VCAP") (class "Default")
      (node (ref "C31") (pin "2") (pinfunction "2_2") (pintype "passive"))
      (node (ref "C32") (pin "2") (pinfunction "2_2") (pintype "passive"))
      (node (ref "U4") (pin "7") (pinfunction "VCAP_7") (pintype "power_in"))
    )
    (net (code "38") (name "/VDD33_1") (class "Default")
      (node (ref "C10") (pin "2") (pinfunction "2_2") (pintype "passive"))
      (node (ref "C11") (pin "2") (pinfunction "2_2") (pintype "passive"))
      (node (ref "C12") (pin "2") (pinfunction "2_2") (pintype "passive"))
      (node (ref "C13") (pin "2") (pinfunction "2_2") (pintype "passive"))
      (node (ref "C9") (pin "2") (pinfunction "2_2") (pintype "passive"))
      (node (ref "L1") (pin "2") (pinfunction "2_2") (pintype "passive"))
      (node (ref "U2") (pin "20") (pinfunction "VDD33_20") (pintype "power_in"))
      (node (ref "U2") (pin "30") (pinfunction "VDD33_30") (pintype "power_in"))
      (node (ref "U2") (pin "48") (pinfunction "VDD33REG_48") (pintype "power_in"))
      (node (ref "U2") (pin "9") (pinfunction "VDD33_9") (pintype "power_in"))
    )
    (net (code "39") (name "/WANRX_N") (class "Default")
      (node (ref "J1") (pin "6") (pinfunction "6_6") (pintype "passive"))
      (node (ref "T1") (pin "9") (pinfunction "RX-_9") (pintype "passive"))
    )
    (net (code "40") (name "/WANRX_P") (class "Default")
      (node (ref "J1") (pin "3") (pinfunction "3_3") (pintype "passive"))
      (node (ref "T1") (pin "11") (pinfunction "RX+_11") (pintype "passive"))
    )
    (net (code "41") (name "/WANTX_N") (class "Default")
      (node (ref "J1") (pin "2") (pinfunction "2_2") (pintype "passive"))
      (node (ref "T1") (pin "14") (pinfunction "TX-_14") (pintype "passive"))
    )
    (net (code "42") (name "/WANTX_P") (class "Default")
      (node (ref "J1") (pin "1") (pinfunction "1_1") (pintype "passive"))
      (node (ref "T1") (pin "16") (pinfunction "TX+_16") (pintype "passive"))
    )
    (net (code "43") (name "/WAN_LED1") (class "Default")
      (node (ref "R4") (pin "1") (pinfunction "1_1") (pintype "passive"))
      (node (ref "U1") (pin "8") (pinfunction "LED6/GPIO_17_8") (pintype "passive"))
    )
    (net (code "44") (name "/WAN_LED2") (class "Default")
      (node (ref "R33") (pin "1") (pinfunction "1_1") (pintype "passive"))
      (node (ref "U1") (pin "12") (pinfunction "GPIO_22_12") (pintype "passive"))
    )
    (net (code "45") (name "/WAN_RX_N") (class "Default")
      (node (ref "R2") (pin "2") (pinfunction "2_2") (pintype "passive"))
      (node (ref "T1") (pin "8") (pinfunction "RD-_8") (pintype "passive"))
      (node (ref "U1") (pin "21") (pinfunction "WAN_PORT_RX-_21") (pintype "passive"))
    )
    (net (code "46") (name "/WAN_RX_P") (class "Default")
      (node (ref "R1") (pin "2") (pinfunction "2_2") (pintype "passive"))
      (node (ref "T1") (pin "6") (pinfunction "RD+_6") (pintype "passive"))
      (node (ref "U1") (pin "20") (pinfunction "WAN_PORT_RX+_20") (pintype "passive"))
    )
    (net (code "47") (name "/WAN_TX_N") (class "Default")
      (node (ref "R6") (pin "2") (pinfunction "2_2") (pintype "passive"))
      (node (ref "T1") (pin "3") (pinfunction "TD-_3") (pintype "passive"))
      (node (ref "U1") (pin "23") (pinfunction "WAN_PORT_TX-_23") (pintype "passive"))
    )
    (net (code "48") (name "/WAN_TX_P") (class "Default")
      (node (ref "R3") (pin "2") (pinfunction "2_2") (pintype "passive"))
      (node (ref "T1") (pin "1") (pinfunction "TD+_1") (pintype "passive"))
      (node (ref "U1") (pin "22") (pinfunction "WAN_PORT_TX+_22") (pintype "passive"))
    )
    (net (code "49") (name "/WIFI_LED") (class "Default")
      (node (ref "LED") (pin "3") (pinfunction "3_3") (pintype "passive"))
      (node (ref "U1") (pin "15") (pinfunction "LED0_15") (pintype "passive"))
      (node (ref "WIFI") (pin "1") (pinfunction "A_1") (pintype "passive"))
    )
    (net (code "50") (name "GND") (class "Default")
      (node (ref "C1") (pin "2") (pinfunction "2_2") (pintype "passive"))
      (node (ref "C10") (pin "1") (pinfunction "1_1") (pintype "passive"))
      (node (ref "C11") (pin "1") (pinfunction "1_1") (pintype "passive"))
      (node (ref "C12") (pin "1") (pinfunction "1_1") (pintype "passive"))
      (node (ref "C13") (pin "1") (pinfunction "1_1") (pintype "passive"))
      (node (ref "C14") (pin "1") (pinfunction "1_1") (pintype "passive"))
      (node (ref "C15") (pin "1") (pinfunction "1_1") (pintype "passive"))
      (node (ref "C16") (pin "1") (pinfunction "1_1") (pintype "passive"))
      (node (ref "C19") (pin "1") (pinfunction "1_1") (pintype "passive"))
      (node (ref "C2") (pin "2") (pinfunction "2_2") (pintype "passive"))
      (node (ref "C20") (pin "1") (pinfunction "1_1") (pintype "passive"))
      (node (ref "C21") (pin "1") (pinfunction "1_1") (pintype "passive"))
      (node (ref "C24") (pin "1") (pinfunction "1_1") (pintype "passive"))
      (node (ref "C25") (pin "1") (pinfunction "1_1") (pintype "passive"))
      (node (ref "C26") (pin "1") (pinfunction "1_1") (pintype "passive"))
      (node (ref "C27") (pin "1") (pinfunction "1_1") (pintype "passive"))
      (node (ref "C29") (pin "1") (pinfunction "1_1") (pintype "passive"))
      (node (ref "C3") (pin "2") (pinfunction "2_2") (pintype "passive"))
      (node (ref "C30") (pin "1") (pinfunction "1_1") (pintype "passive"))
      (node (ref "C31") (pin "1") (pinfunction "1_1") (pintype "passive"))
      (node (ref "C32") (pin "1") (pinfunction "1_1") (pintype "passive"))
      (node (ref "C33") (pin "1") (pinfunction "1_1") (pintype "passive"))
      (node (ref "C34") (pin "1") (pinfunction "1_1") (pintype "passive"))
      (node (ref "C35") (pin "1") (pinfunction "1_1") (pintype "passive"))
      (node (ref "C36") (pin "1") (pinfunction "1_1") (pintype "passive"))
      (node (ref "C37") (pin "1") (pinfunction "1_1") (pintype "passive"))
      (node (ref "C39") (pin "1") (pinfunction "1_1") (pintype "passive"))
      (node (ref "C40") (pin "1") (pinfunction "1_1") (pintype "passive"))
      (node (ref "C41") (pin "1") (pinfunction "1_1") (pintype "passive"))
      (node (ref "C42") (pin "1") (pinfunction "1_1") (pintype "passive"))
      (node (ref "C44") (pin "1") (pinfunction "1_1") (pintype "passive"))
      (node (ref "C45") (pin "1") (pinfunction "1_1") (pintype "passive"))
      (node (ref "C46") (pin "1") (pinfunction "1_1") (pintype "passive"))
      (node (ref "C47") (pin "1") (pinfunction "1_1") (pintype "passive"))
      (node (ref "C5") (pin "2") (pinfunction "2_2") (pintype "passive"))
      (node (ref "C6") (pin "2") (pinfunction "2_2") (pintype "passive"))
      (node (ref "C7") (pin "2") (pinfunction "2_2") (pintype "passive"))
      (node (ref "C8") (pin "2") (pinfunction "2_2") (pintype "passive"))
      (node (ref "C9") (pin "1") (pinfunction "1_1") (pintype "passive"))
      (node (ref "DEBUG") (pin "3") (pinfunction "3_3") (pintype "passive"))
      (node (ref "GND") (pin "1") (pinfunction "1_1") (pintype "passive"))
      (node (ref "ICSP") (pin "3") (pinfunction "3_3") (pintype "passive"))
      (node (ref "ICSP") (pin "6") (pinfunction "6_6") (pintype "passive"))
      (node (ref "J1") (pin "11") (pinfunction "LED2-_11") (pintype "passive"))
      (node (ref "J1") (pin "9") (pinfunction "LED1-_9") (pintype "passive"))
      (node (ref "J2") (pin "1") (pinfunction "1_1") (pintype "passive"))
      (node (ref "J2") (pin "2") (pinfunction "2_2") (pintype "passive"))
      (node (ref "J2") (pin "3") (pinfunction "3_3") (pintype "passive"))
      (node (ref "J2") (pin "4") (pinfunction "4_4") (pintype "passive"))
      (node (ref "L3") (pin "1") (pinfunction "1_1") (pintype "passive"))
      (node (ref "LAN") (pin "7") (pinfunction "7_7") (pintype "passive"))
      (node (ref "LAN") (pin "8") (pinfunction "8_8") (pintype "passive"))
      (node (ref "POWER") (pin "1") (pinfunction "1_1") (pintype "passive"))
      (node (ref "POWER") (pin "2") (pinfunction "2_2") (pintype "passive"))
      (node (ref "PWR") (pin "2") (pinfunction "K_2") (pintype "passive"))
      (node (ref "Q1") (pin "2") (pinfunction "E_2") (pintype "passive"))
      (node (ref "R26") (pin "1") (pinfunction "1_1") (pintype "passive"))
      (node (ref "R28") (pin "2") (pinfunction "2_2") (pintype "passive"))
      (node (ref "R32") (pin "1") (pinfunction "1_1") (pintype "passive"))
      (node (ref "R35") (pin "1") (pinfunction "1_1") (pintype "passive"))
      (node (ref "R5") (pin "2") (pinfunction "2_2") (pintype "passive"))
      (node (ref "U1") (pin "1") (pinfunction "GND_1") (pintype "passive"))
      (node (ref "U1") (pin "18") (pinfunction "GND_18") (pintype "passive"))
      (node (ref "U1") (pin "19") (pinfunction "GND_19") (pintype "passive"))
      (node (ref "U1") (pin "3") (pinfunction "GND_3") (pintype "passive"))
      (node (ref "U1") (pin "36") (pinfunction "GND_36") (pintype "passive"))
      (node (ref "U1") (pin "40") (pinfunction "GND_40") (pintype "passive"))
      (node (ref "U2") (pin "14") (pinfunction "TEST_14") (pintype "passive"))
      (node (ref "U2") (pin "2") (pinfunction "VSSREG_2") (pintype "power_in"))
      (node (ref "U2") (pin "23") (pinfunction "VSS_23") (pintype "power_in"))
      (node (ref "U2") (pin "27") (pinfunction "VSS_27") (pintype "power_in"))
      (node (ref "U2") (pin "28") (pinfunction "DM2_28") (pintype "passive"))
      (node (ref "U2") (pin "29") (pinfunction "DP2_29") (pintype "passive"))
      (node (ref "U2") (pin "31") (pinfunction "DM3_31") (pintype "passive"))
      (node (ref "U2") (pin "32") (pinfunction "DP3_32") (pintype "passive"))
      (node (ref "U2") (pin "34") (pinfunction "DM4_34") (pintype "passive"))
      (node (ref "U2") (pin "35") (pinfunction "DP4_35") (pintype "passive"))
      (node (ref "U2") (pin "36") (pinfunction "VSS_36") (pintype "power_in"))
      (node (ref "U2") (pin "38") (pinfunction "PPB4_38") (pintype "passive"))
      (node (ref "U2") (pin "39") (pinfunction "CSB4_39") (pintype "passive"))
      (node (ref "U2") (pin "40") (pinfunction "PPB3_40") (pintype "passive"))
      (node (ref "U2") (pin "41") (pinfunction "CSB3_41") (pintype "passive"))
      (node (ref "U2") (pin "42") (pinfunction "VSS_42") (pintype "power_in"))
      (node (ref "U2") (pin "43") (pinfunction "PPB2_43") (pintype "passive"))
      (node (ref "U2") (pin "44") (pinfunction "CSB2_44") (pintype "passive"))
      (node (ref "U2") (pin "5") (pinfunction "LED2_5") (pintype "passive"))
      (node (ref "U2") (pin "6") (pinfunction "LED1_6") (pintype "passive"))
      (node (ref "U4") (pin "16") (pinfunction "AVSS_16") (pintype "power_in"))
      (node (ref "U4") (pin "29") (pinfunction "VSS_29") (pintype "power_in"))
      (node (ref "U4") (pin "39") (pinfunction "VSS_39") (pintype "power_in"))
      (node (ref "U4") (pin "6") (pinfunction "VSS_6") (pintype "power_in"))
      (node (ref "UART1") (pin "4") (pinfunction "4_4") (pintype "passive"))
      (node (ref "UART1") (pin "8") (pinfunction "8_8") (pintype "passive"))
      (node (ref "UART2") (pin "4") (pinfunction "4_4") (pintype "passive"))
      (node (ref "UART2") (pin "8") (pinfunction "8_8") (pintype "passive"))
    )
    (net (code "51") (name "NET_POW") (class "Default")
      (node (ref "C3") (pin "1") (pinfunction "1_1") (pintype "passive"))
      (node (ref "C8") (pin "1") (pinfunction "1_1") (pintype "passive"))
      (node (ref "LAN") (pin "1") (pinfunction "1_1") (pintype "passive"))
      (node (ref "T1") (pin "2") (pinfunction "CTD_2") (pintype "passive"))
      (node (ref "T1") (pin "7") (pinfunction "CRD_7") (pintype "passive"))
      (node (ref "U1") (pin "39") (pinfunction "VDD_2.0V_OUTPUT_39") (pintype "passive"))
    )
    (net (code "52") (name "Net-(AR-K)") (class "Default")
      (node (ref "AR") (pin "2") (pinfunction "K_2") (pintype "passive"))
      (node (ref "R35") (pin "2") (pinfunction "2_2") (pintype "passive"))
    )
    (net (code "53") (name "Net-(C1-Pad1)") (class "Default")
      (node (ref "C1") (pin "1") (pinfunction "1_1") (pintype "passive"))
      (node (ref "R1") (pin "1") (pinfunction "1_1") (pintype "passive"))
      (node (ref "R2") (pin "1") (pinfunction "1_1") (pintype "passive"))
    )
    (net (code "54") (name "Net-(C2-Pad1)") (class "Default")
      (node (ref "C2") (pin "1") (pinfunction "1_1") (pintype "passive"))
      (node (ref "R3") (pin "1") (pinfunction "1_1") (pintype "passive"))
      (node (ref "R6") (pin "1") (pinfunction "1_1") (pintype "passive"))
    )
    (net (code "55") (name "Net-(C4-Pad1)") (class "Default")
      (node (ref "C4") (pin "1") (pinfunction "1_1") (pintype "passive"))
      (node (ref "C6") (pin "1") (pinfunction "1_1") (pintype "passive"))
      (node (ref "J1") (pin "13") (pinfunction "SHIELD_13") (pintype "passive"))
      (node (ref "J1") (pin "14") (pinfunction "SHIELD_14") (pintype "passive"))
    )
    (net (code "56") (name "Net-(C4-Pad2)") (class "Default")
      (node (ref "C4") (pin "2") (pinfunction "2_2") (pintype "passive"))
      (node (ref "R10") (pin "2") (pinfunction "2_2") (pintype "passive"))
      (node (ref "R7") (pin "2") (pinfunction "2_2") (pintype "passive"))
      (node (ref "R8") (pin "2") (pinfunction "2_2") (pintype "passive"))
      (node (ref "R9") (pin "2") (pinfunction "2_2") (pintype "passive"))
    )
    (net (code "57") (name "Net-(C5-Pad1)") (class "Default")
      (node (ref "C5") (pin "1") (pinfunction "1_1") (pintype "passive"))
      (node (ref "R11") (pin "1") (pinfunction "1_1") (pintype "passive"))
      (node (ref "R12") (pin "1") (pinfunction "1_1") (pintype "passive"))
    )
    (net (code "58") (name "Net-(C7-Pad1)") (class "Default")
      (node (ref "C7") (pin "1") (pinfunction "1_1") (pintype "passive"))
      (node (ref "R13") (pin "1") (pinfunction "1_1") (pintype "passive"))
      (node (ref "R14") (pin "1") (pinfunction "1_1") (pintype "passive"))
    )
    (net (code "59") (name "Net-(C22-Pad2)") (class "Default")
      (node (ref "C22") (pin "2") (pinfunction "2_2") (pintype "passive"))
      (node (ref "C23") (pin "2") (pinfunction "2_2") (pintype "passive"))
      (node (ref "L2") (pin "2") (pinfunction "2_2") (pintype "passive"))
      (node (ref "U2") (pin "17") (pinfunction "AVDD_17") (pintype "power_in"))
      (node (ref "U2") (pin "19") (pinfunction "AVDD_19") (pintype "power_in"))
    )
    (net (code "60") (name "Net-(D3-A)") (class "Default")
      (node (ref "D3") (pin "1") (pinfunction "A_1") (pintype "passive"))
      (node (ref "LS1") (pin "2") (pinfunction "B_2") (pintype "passive"))
      (node (ref "Q1") (pin "3") (pinfunction "C_3") (pintype "passive"))
    )
    (net (code "61") (name "Net-(ICSP-Pad1)") (class "Default")
      (node (ref "ICSP") (pin "1") (pinfunction "1_1") (pintype "passive"))
      (node (ref "R27") (pin "2") (pinfunction "2_2") (pintype "passive"))
    )
    (net (code "62") (name "Net-(ICSP-Pad4)") (class "Default")
      (node (ref "ICSP") (pin "4") (pinfunction "4_4") (pintype "passive"))
      (node (ref "R29") (pin "2") (pinfunction "2_2") (pintype "passive"))
    )
    (net (code "63") (name "Net-(ICSP-Pad5)") (class "Default")
      (node (ref "ICSP") (pin "5") (pinfunction "5_5") (pintype "passive"))
      (node (ref "R30") (pin "2") (pinfunction "2_2") (pintype "passive"))
    )
    (net (code "64") (name "Net-(J1-LED1+)") (class "Default")
      (node (ref "J1") (pin "10") (pinfunction "LED1+_10") (pintype "passive"))
      (node (ref "R4") (pin "2") (pinfunction "2_2") (pintype "passive"))
    )
    (net (code "65") (name "Net-(J1-LED2+)") (class "Default")
      (node (ref "J1") (pin "12") (pinfunction "LED2+_12") (pintype "passive"))
      (node (ref "R33") (pin "2") (pinfunction "2_2") (pintype "passive"))
    )
    (net (code "66") (name "Net-(J1-Pad4)") (class "Default")
      (node (ref "J1") (pin "4") (pinfunction "4_4") (pintype "passive"))
      (node (ref "J1") (pin "5") (pinfunction "5_5") (pintype "passive"))
      (node (ref "R9") (pin "1") (pinfunction "1_1") (pintype "passive"))
    )
    (net (code "67") (name "Net-(J1-Pad7)") (class "Default")
      (node (ref "J1") (pin "7") (pinfunction "7_7") (pintype "passive"))
      (node (ref "J1") (pin "8") (pinfunction "8_8") (pintype "passive"))
      (node (ref "R10") (pin "1") (pinfunction "1_1") (pintype "passive"))
    )
    (net (code "68") (name "Net-(LED-Pad2)") (class "Default")
      (node (ref "LED") (pin "2") (pinfunction "2_2") (pintype "passive"))
      (node (ref "R5") (pin "1") (pinfunction "1_1") (pintype "passive"))
    )
    (net (code "69") (name "Net-(LED-Pad4)") (class "Default")
      (node (ref "LED") (pin "4") (pinfunction "4_4") (pintype "passive"))
      (node (ref "R28") (pin "1") (pinfunction "1_1") (pintype "passive"))
    )
    (net (code "70") (name "Net-(PWR-A)") (class "Default")
      (node (ref "PWR") (pin "1") (pinfunction "A_1") (pintype "passive"))
      (node (ref "R24") (pin "1") (pinfunction "1_1") (pintype "passive"))
    )
    (net (code "71") (name "Net-(Q1-B)") (class "Default")
      (node (ref "Q1") (pin "1") (pinfunction "B_1") (pintype "passive"))
      (node (ref "R25") (pin "1") (pinfunction "1_1") (pintype "passive"))
    )
    (net (code "72") (name "Net-(RUN-A)") (class "Default")
      (node (ref "R22") (pin "1") (pinfunction "1_1") (pintype "passive"))
      (node (ref "RUN") (pin "1") (pinfunction "A_1") (pintype "passive"))
    )
    (net (code "73") (name "Net-(T1-CRX)") (class "Default")
      (node (ref "R7") (pin "1") (pinfunction "1_1") (pintype "passive"))
      (node (ref "T1") (pin "10") (pinfunction "CRX_10") (pintype "passive"))
    )
    (net (code "74") (name "Net-(T1-CTX)") (class "Default")
      (node (ref "R8") (pin "1") (pinfunction "1_1") (pintype "passive"))
      (node (ref "T1") (pin "15") (pinfunction "CTX_15") (pintype "passive"))
    )
    (net (code "75") (name "Net-(U1-JUMPSTART{slash}UART_RTS)") (class "Default")
      (node (ref "S2") (pin "1") (pinfunction "1_1") (pintype "passive"))
      (node (ref "U1") (pin "48") (pinfunction "JUMPSTART/UART_RTS_48") (pintype "passive"))
    )
    (net (code "76") (name "Net-(U2-AMBER)") (class "Default")
      (node (ref "U2") (pin "7") (pinfunction "AMBER_7") (pintype "passive"))
      (node (ref "U2") (pin "8") (pinfunction "GREEN_8") (pintype "passive"))
    )
    (net (code "77") (name "Net-(U2-AVSS(R))") (class "Default")
      (node (ref "C22") (pin "1") (pinfunction "1_1") (pintype "passive"))
      (node (ref "C23") (pin "1") (pinfunction "1_1") (pintype "passive"))
      (node (ref "L3") (pin "2") (pinfunction "2_2") (pintype "passive"))
      (node (ref "R16") (pin "1") (pinfunction "1_1") (pintype "passive"))
      (node (ref "U2") (pin "16") (pinfunction "AVSS(R)_16") (pintype "power_in"))
      (node (ref "U2") (pin "18") (pinfunction "AVSS_18") (pintype "power_in"))
    )
    (net (code "78") (name "Net-(U2-CSB1)") (class "Default")
      (node (ref "R18") (pin "1") (pinfunction "1_1") (pintype "passive"))
      (node (ref "U2") (pin "46") (pinfunction "CSB1_46") (pintype "passive"))
    )
    (net (code "79") (name "Net-(U2-PPB1)") (class "Default")
      (node (ref "R17") (pin "1") (pinfunction "1_1") (pintype "passive"))
      (node (ref "U2") (pin "45") (pinfunction "PPB1_45") (pintype "passive"))
    )
    (net (code "80") (name "Net-(U2-RREF)") (class "Default")
      (node (ref "R16") (pin "2") (pinfunction "2_2") (pintype "passive"))
      (node (ref "U2") (pin "15") (pinfunction "RREF_15") (pintype "passive"))
    )
    (net (code "81") (name "Net-(U2-VBUSM)") (class "Default")
      (node (ref "R15") (pin "2") (pinfunction "2_2") (pintype "passive"))
      (node (ref "U2") (pin "47") (pinfunction "VBUSM_47") (pintype "input"))
    )
    (net (code "82") (name "Net-(U2-X1)") (class "Default")
      (node (ref "R20") (pin "1") (pinfunction "1_1") (pintype "passive"))
      (node (ref "U2") (pin "10") (pinfunction "X1_10") (pintype "input"))
    )
    (net (code "83") (name "Net-(U2-X2)") (class "Default")
      (node (ref "C26") (pin "2") (pinfunction "2_2") (pintype "passive"))
      (node (ref "R21") (pin "1") (pinfunction "1_1") (pintype "passive"))
      (node (ref "U2") (pin "11") (pinfunction "X2_11") (pintype "output"))
      (node (ref "Y1") (pin "1") (pinfunction "OSC1_1") (pintype "passive"))
    )
    (net (code "84") (name "Net-(U4-OSC1{slash}CLKI{slash}RPA2{slash}RA2)") (class "Default")
      (node (ref "C44") (pin "2") (pinfunction "2_2") (pintype "passive"))
      (node (ref "U4") (pin "30") (pinfunction "OSC1/CLKI/RPA2/RA2_30") (pintype "passive"))
      (node (ref "Y2") (pin "2") (pinfunction "OSC2_2") (pintype "passive"))
    )
    (net (code "85") (name "Net-(U4-OSC2{slash}CLKO{slash}RPA3{slash}RA3)") (class "Default")
      (node (ref "R31") (pin "2") (pinfunction "2_2") (pintype "passive"))
      (node (ref "U4") (pin "31") (pinfunction "OSC2/CLKO/RPA3/RA3_31") (pintype "passive"))
    )
    (net (code "86") (name "Net-(WIFI-K)") (class "Default")
      (node (ref "R32") (pin "2") (pinfunction "2_2") (pintype "passive"))
      (node (ref "WIFI") (pin "2") (pinfunction "K_2") (pintype "passive"))
    )
    (net (code "87") (name "Net-(Y2-OSC1)") (class "Default")
      (node (ref "C46") (pin "2") (pinfunction "2_2") (pintype "passive"))
      (node (ref "R31") (pin "1") (pinfunction "1_1") (pintype "passive"))
      (node (ref "Y2") (pin "1") (pinfunction "OSC1_1") (pintype "passive"))
    )
    (net (code "88") (name "VDD2V5_1") (class "Default")
      (node (ref "C14") (pin "2") (pinfunction "2_2") (pintype "passive"))
      (node (ref "C15") (pin "2") (pinfunction "2_2") (pintype "passive"))
      (node (ref "C16") (pin "2") (pinfunction "2_2") (pintype "passive"))
      (node (ref "C19") (pin "2") (pinfunction "2_2") (pintype "passive"))
      (node (ref "C20") (pin "2") (pinfunction "2_2") (pintype "passive"))
      (node (ref "C21") (pin "2") (pinfunction "2_2") (pintype "passive"))
      (node (ref "L2") (pin "1") (pinfunction "1_1") (pintype "passive"))
      (node (ref "TP1") (pin "1") (pinfunction "1_1") (pintype "passive"))
      (node (ref "U2") (pin "1") (pinfunction "VDD25OUT_1") (pintype "power_in"))
      (node (ref "U2") (pin "12") (pinfunction "VDD25_12") (pintype "power_in"))
      (node (ref "U2") (pin "24") (pinfunction "VDD25_24") (pintype "power_in"))
      (node (ref "U2") (pin "33") (pinfunction "VDD25_33") (pintype "power_in"))
    )
    (net (code "89") (name "VDD3V3") (class "Default")
      (node (ref "C27") (pin "2") (pinfunction "2_2") (pintype "passive"))
      (node (ref "C29") (pin "2") (pinfunction "2_2") (pintype "passive"))
      (node (ref "C30") (pin "2") (pinfunction "2_2") (pintype "passive"))
      (node (ref "C33") (pin "2") (pinfunction "2_2") (pintype "passive"))
      (node (ref "C34") (pin "2") (pinfunction "2_2") (pintype "passive"))
      (node (ref "C35") (pin "2") (pinfunction "2_2") (pintype "passive"))
      (node (ref "C36") (pin "2") (pinfunction "2_2") (pintype "passive"))
      (node (ref "C37") (pin "2") (pinfunction "2_2") (pintype "passive"))
      (node (ref "C39") (pin "2") (pinfunction "2_2") (pintype "passive"))
      (node (ref "C40") (pin "2") (pinfunction "2_2") (pintype "passive"))
      (node (ref "C41") (pin "2") (pinfunction "2_2") (pintype "passive"))
      (node (ref "C42") (pin "2") (pinfunction "2_2") (pintype "passive"))
      (node (ref "C45") (pin "2") (pinfunction "2_2") (pintype "passive"))
      (node (ref "D3") (pin "2") (pinfunction "K_2") (pintype "passive"))
      (node (ref "ICSP") (pin "2") (pinfunction "2_2") (pintype "passive"))
      (node (ref "L1") (pin "1") (pinfunction "1_1") (pintype "passive"))
      (node (ref "LS1") (pin "1") (pinfunction "A_1") (pintype "passive"))
      (node (ref "POWER") (pin "3") (pinfunction "3_3") (pintype "passive"))
      (node (ref "POWER") (pin "4") (pinfunction "4_4") (pintype "passive"))
      (node (ref "R15") (pin "1") (pinfunction "1_1") (pintype "passive"))
      (node (ref "R17") (pin "2") (pinfunction "2_2") (pintype "passive"))
      (node (ref "R18") (pin "2") (pinfunction "2_2") (pintype "passive"))
      (node (ref "R19") (pin "2") (pinfunction "2_2") (pintype "passive"))
      (node (ref "R22") (pin "2") (pinfunction "2_2") (pintype "passive"))
      (node (ref "R23") (pin "2") (pinfunction "2_2") (pintype "passive"))
      (node (ref "R24") (pin "2") (pinfunction "2_2") (pintype "passive"))
      (node (ref "R34") (pin "2") (pinfunction "2_2") (pintype "passive"))
      (node (ref "R43") (pin "2") (pinfunction "2_2") (pintype "passive"))
      (node (ref "S2") (pin "2") (pinfunction "2_2") (pintype "passive"))
      (node (ref "TP4") (pin "1") (pinfunction "1_1") (pintype "passive"))
      (node (ref "U1") (pin "37") (pinfunction "VDD_3.3V_37") (pintype "passive"))
      (node (ref "U1") (pin "38") (pinfunction "VDD_3.3V_38") (pintype "passive"))
      (node (ref "U2") (pin "13") (pinfunction "BUS_B_13") (pintype "input"))
      (node (ref "U2") (pin "3") (pinfunction "LED4_3") (pintype "passive"))
      (node (ref "U2") (pin "4") (pinfunction "LED3_4") (pintype "passive"))
      (node (ref "U4") (pin "10") (pinfunction "VUSB3V3_10") (pintype "power_in"))
      (node (ref "U4") (pin "17") (pinfunction "AVDD_17") (pintype "power_in"))
      (node (ref "U4") (pin "28") (pinfunction "VDD_28") (pintype "power_in"))
      (node (ref "U4") (pin "40") (pinfunction "VDD_40") (pintype "power_in"))
      (node (ref "U4") (pin "42") (pinfunction "VBUS_42") (pintype "power_in"))
    )
    (net (code "90") (name "unconnected-(M1-Pad1)") (class "Default")
      (node (ref "M1") (pin "1") (pinfunction "1_1") (pintype "passive+no_connect"))
    )
    (net (code "91") (name "unconnected-(M2-Pad1)") (class "Default")
      (node (ref "M2") (pin "1") (pinfunction "1_1") (pintype "passive+no_connect"))
    )
    (net (code "92") (name "unconnected-(M3-PIN-Pad0)") (class "Default")
      (node (ref "M3") (pin "0") (pinfunction "PIN_0") (pintype "power_in"))
    )
    (net (code "93") (name "unconnected-(M4-PIN-Pad0)") (class "Default")
      (node (ref "M4") (pin "0") (pinfunction "PIN_0") (pintype "power_in"))
    )
    (net (code "94") (name "unconnected-(M5-PIN-Pad0)") (class "Default")
      (node (ref "M5") (pin "0") (pinfunction "PIN_0") (pintype "power_in"))
    )
    (net (code "95") (name "unconnected-(M6-PIN-Pad0)") (class "Default")
      (node (ref "M6") (pin "0") (pinfunction "PIN_0") (pintype "power_in"))
    )
    (net (code "96") (name "unconnected-(U1-ANTENNA-Pad2)") (class "Default")
      (node (ref "U1") (pin "2") (pinfunction "ANTENNA_2") (pintype "passive+no_connect"))
    )
    (net (code "97") (name "unconnected-(U1-LAN_PORT1_RX+-Pad34)") (class "Default")
      (node (ref "U1") (pin "34") (pinfunction "LAN_PORT1_RX+_34") (pintype "passive+no_connect"))
    )
    (net (code "98") (name "unconnected-(U1-LAN_PORT1_RX--Pad35)") (class "Default")
      (node (ref "U1") (pin "35") (pinfunction "LAN_PORT1_RX-_35") (pintype "passive+no_connect"))
    )
    (net (code "99") (name "unconnected-(U1-LAN_PORT1_TX+-Pad32)") (class "Default")
      (node (ref "U1") (pin "32") (pinfunction "LAN_PORT1_TX+_32") (pintype "passive+no_connect"))
    )
    (net (code "100") (name "unconnected-(U1-LAN_PORT1_TX--Pad33)") (class "Default")
      (node (ref "U1") (pin "33") (pinfunction "LAN_PORT1_TX-_33") (pintype "passive+no_connect"))
    )
    (net (code "101") (name "unconnected-(U1-LAN_PORT2_RX+-Pad28)") (class "Default")
      (node (ref "U1") (pin "28") (pinfunction "LAN_PORT2_RX+_28") (pintype "passive+no_connect"))
    )
    (net (code "102") (name "unconnected-(U1-LAN_PORT2_RX--Pad29)") (class "Default")
      (node (ref "U1") (pin "29") (pinfunction "LAN_PORT2_RX-_29") (pintype "passive+no_connect"))
    )
    (net (code "103") (name "unconnected-(U1-LAN_PORT2_TX+-Pad30)") (class "Default")
      (node (ref "U1") (pin "30") (pinfunction "LAN_PORT2_TX+_30") (pintype "passive+no_connect"))
    )
    (net (code "104") (name "unconnected-(U1-LAN_PORT2_TX--Pad31)") (class "Default")
      (node (ref "U1") (pin "31") (pinfunction "LAN_PORT2_TX-_31") (pintype "passive+no_connect"))
    )
    (net (code "105") (name "unconnected-(U1-LAN_PORT3_RX+-Pad26)") (class "Default")
      (node (ref "U1") (pin "26") (pinfunction "LAN_PORT3_RX+_26") (pintype "passive+no_connect"))
    )
    (net (code "106") (name "unconnected-(U1-LAN_PORT3_RX--Pad27)") (class "Default")
      (node (ref "U1") (pin "27") (pinfunction "LAN_PORT3_RX-_27") (pintype "passive+no_connect"))
    )
    (net (code "107") (name "unconnected-(U1-LAN_PORT3_TX+-Pad24)") (class "Default")
      (node (ref "U1") (pin "24") (pinfunction "LAN_PORT3_TX+_24") (pintype "passive+no_connect"))
    )
    (net (code "108") (name "unconnected-(U1-LAN_PORT3_TX--Pad25)") (class "Default")
      (node (ref "U1") (pin "25") (pinfunction "LAN_PORT3_TX-_25") (pintype "passive+no_connect"))
    )
    (net (code "109") (name "unconnected-(U1-LED3-Pad11)") (class "Default")
      (node (ref "U1") (pin "11") (pinfunction "LED3_11") (pintype "passive+no_connect"))
    )
    (net (code "110") (name "unconnected-(U1-LED4-Pad10)") (class "Default")
      (node (ref "U1") (pin "10") (pinfunction "LED4_10") (pintype "passive+no_connect"))
    )
    (net (code "111") (name "unconnected-(U1-LED5-Pad9)") (class "Default")
      (node (ref "U1") (pin "9") (pinfunction "LED5_9") (pintype "passive+no_connect"))
    )
    (net (code "112") (name "unconnected-(U1-RESET_CONFIG{slash}UART_CTS-Pad7)") (class "Default")
      (node (ref "U1") (pin "7") (pinfunction "RESET_CONFIG/UART_CTS_7") (pintype "passive+no_connect"))
    )
    (net (code "113") (name "unconnected-(U1-SPI_CLK-Pad5)") (class "Default")
      (node (ref "U1") (pin "5") (pinfunction "SPI_CLK_5") (pintype "passive+no_connect"))
    )
    (net (code "114") (name "unconnected-(U1-SPI_MISO-Pad6)") (class "Default")
      (node (ref "U1") (pin "6") (pinfunction "SPI_MISO_6") (pintype "passive+no_connect"))
    )
    (net (code "115") (name "unconnected-(U1-SPI_MOSI-Pad4)") (class "Default")
      (node (ref "U1") (pin "4") (pinfunction "SPI_MOSI_4") (pintype "passive+no_connect"))
    )
    (net (code "116") (name "unconnected-(U4-AN7{slash}RPC1{slash}RC1-Pad26)") (class "Default")
      (node (ref "U4") (pin "26") (pinfunction "AN7/RPC1/RC1_26") (pintype "bidirectional+no_connect"))
    )
    (net (code "117") (name "unconnected-(U4-AN9{slash}C3INA{slash}RPB15{slash}SCK2{slash}CTED6{slash}PMCS1{slash}RB15-Pad15)") (class "Default")
      (node (ref "U4") (pin "15") (pinfunction "AN9/C3INA/RPB15/SCK2/CTED6/PMCS1/RB15_15") (pintype "bidirectional+no_connect"))
    )
    (net (code "118") (name "unconnected-(U4-AN11{slash}RPB13{slash}CTPLS{slash}PMRD{slash}RB13-Pad11)") (class "Default")
      (node (ref "U4") (pin "11") (pinfunction "AN11/RPB13/CTPLS/PMRD/RB13_11") (pintype "bidirectional+no_connect"))
    )
    (net (code "119") (name "unconnected-(U4-CVREFOUT{slash}AN10{slash}C3INB{slash}RPB14{slash}VBUSON{slash}SCK1{slash}CTED5{slash}RB14-Pad14)") (class "Default")
      (node (ref "U4") (pin "14") (pinfunction "CVREFOUT/AN10/C3INB/RPB14/VBUSON/SCK1/CTED5/RB14_14") (pintype "bidirectional+no_connect"))
    )
    (net (code "120") (name "unconnected-(U4-PGEC3{slash}VREF-{slash}CVREF-{slash}AN1{slash}RPA1{slash}CTED2{slash}PMD6{slash}RA1-Pad20)") (class "Default")
      (node (ref "U4") (pin "20") (pinfunction "PGEC3/VREF-/CVREF-/AN1/RPA1/CTED2/PMD6/RA1_20") (pintype "bidirectional+no_connect"))
    )
    (net (code "121") (name "unconnected-(U4-PGED3{slash}VREF+{slash}CVREF+{slash}AN0{slash}C3INC{slash}RPA0{slash}CTED1{slash}PMD7{slash}RA0-Pad19)") (class "Default")
      (node (ref "U4") (pin "19") (pinfunction "PGED3/VREF+/CVREF+/AN0/C3INC/RPA0/CTED1/PMD7/RA0_19") (pintype "bidirectional+no_connect"))
    )
    (net (code "122") (name "unconnected-(U4-TDI{slash}RPA9{slash}PMA9{slash}RA9-Pad35)") (class "Default")
      (node (ref "U4") (pin "35") (pinfunction "TDI/RPA9/PMA9/RA9_35") (pintype "bidirectional+no_connect"))
    )
    (net (code "123") (name "unconnected-(U4-TDO{slash}RPA8{slash}PMA8{slash}RA8-Pad32)") (class "Default")
      (node (ref "U4") (pin "32") (pinfunction "TDO/RPA8/PMA8/RA8_32") (pintype "bidirectional+no_connect"))
    )
  )
)
